# test.net
KiCad netlist of a schematic drawn in Altium Designer
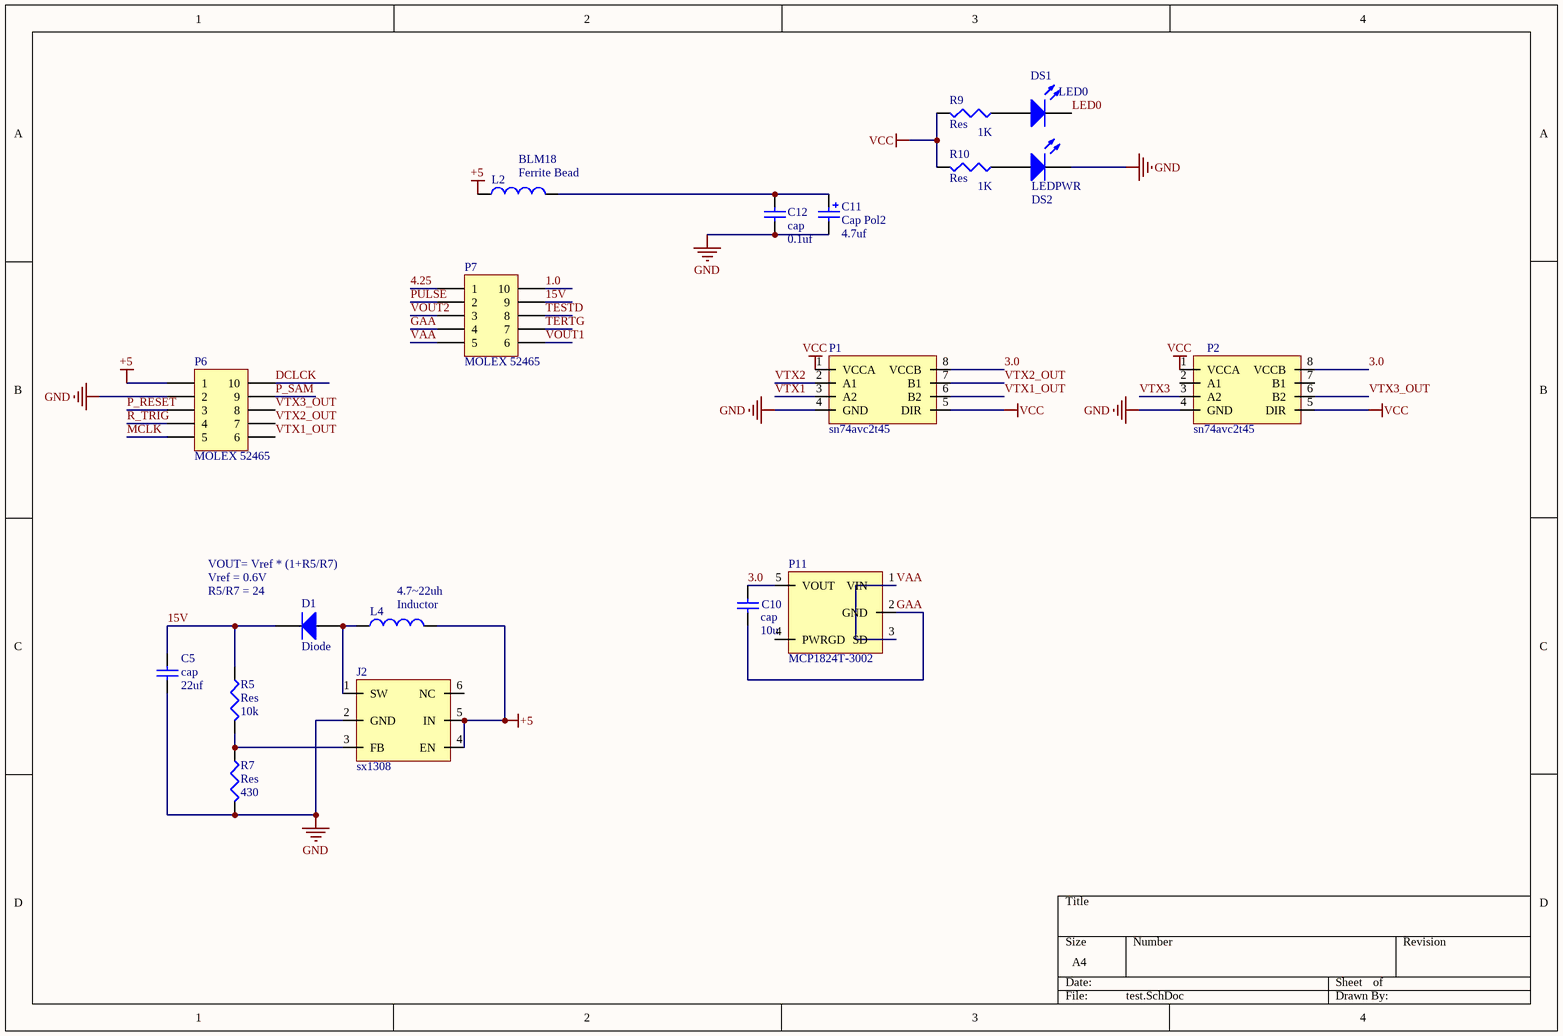
[diagram p0: test.SchDoc]

(export (version "E")
  (design (tool "Eeschema 10.0.6"))
  (components
    (comp (ref "C5")
      (value "cap")
      (footprint "J1-0603")
      (description "Capacitor (Semiconductor SIM Model)")
      (fields (field (name "ALTIUM_VALUE") "22uf") (field (name "PUBLISHER") "Altium Limited"))
      (libsource (lib "Miscellaneous Devices") (part "Cap Semi"))
    )
    (comp (ref "C10")
      (value "cap")
      (footprint "J1-0603")
      (description "Capacitor (Semiconductor SIM Model)")
      (fields (field (name "ALTIUM_VALUE") "10u") (field (name "PUBLISHER") "Altium Limited"))
      (libsource (lib "Miscellaneous Devices") (part "Cap Semi"))
    )
    (comp (ref "C11")
      (value "Cap Pol2")
      (footprint "C1206+")
      (description "Polarized Capacitor (Axial)")
      (fields (field (name "ALTIUM_VALUE") "4.7uf") (field (name "PUBLISHER") "Altium Limited"))
      (libsource (lib "Miscellaneous Devices") (part "Cap Pol2"))
    )
    (comp (ref "C12")
      (value "cap")
      (footprint "J1-0603")
      (description "Capacitor (Semiconductor SIM Model)")
      (fields (field (name "ALTIUM_VALUE") "0.1uf") (field (name "PUBLISHER") "Altium Limited"))
      (libsource (lib "Miscellaneous Devices") (part "Cap Semi"))
    )
    (comp (ref "D1")
      (value "Diode")
      (footprint "D1206")
      (description "Default Diode")
      (fields (field (name "PUBLISHER") "Altium Limited"))
      (libsource (lib "Miscellaneous Devices") (part "Diode"))
    )
    (comp (ref "DS1")
      (value "LED0")
      (footprint "SMDLED")
      (description "Typical RED, GREEN, YELLOW, AMBER GaAs LED")
      (fields (field (name "PUBLISHER") "Altium Limited"))
      (libsource (lib "2014ﾄ鷭STM32F4 Exploerｿｪｷ｢ｰ・V1.4_ｽﾌｳﾌﾂﾒｸﾄｰ觸EXPLORER") (part "LED2"))
    )
    (comp (ref "DS2")
      (value "LEDPWR")
      (footprint "SMDLED")
      (description "Typical RED, GREEN, YELLOW, AMBER GaAs LED")
      (fields (field (name "PUBLISHER") "Altium Limited"))
      (libsource (lib "2014ﾄ鷭STM32F4 Exploerｿｪｷ｢ｰ・V1.4_ｽﾌｳﾌﾂﾒｸﾄｰ觸EXPLORER") (part "LED2"))
    )
    (comp (ref "J2") (value "sx1308") (footprint "sot23-6") (libsource (lib "jskschemlib") (part "sx1308")))
    (comp (ref "L2")
      (value "Ferrite Bead")
      (footprint "J1-0603")
      (description "Inductor")
      (fields (field (name "ALTIUM_VALUE") "BLM18") (field (name "PUBLISHER") "Altium Limited"))
      (libsource (lib "Miscellaneous Devices") (part "Inductor"))
    )
    (comp (ref "L4")
      (value "Inductor")
      (footprint "induct4*4")
      (fields (field (name "ALTIUM_VALUE") "4.7~22uh") (field (name "PUBLISHER") "Altium Limited"))
      (libsource (lib "Miscellaneous Devices") (part "Inductor"))
    )
    (comp (ref "P1")
      (value "sn74avc2t45")
      (footprint "TSSOP8")
      (libsource (lib "jskschemlib") (part "sn74avc2t45"))
    )
    (comp (ref "P2")
      (value "sn74avc2t45")
      (footprint "TSSOP8")
      (libsource (lib "jskschemlib") (part "sn74avc2t45"))
    )
    (comp (ref "P6")
      (value "MOLEX 52465")
      (footprint "btb10p_m")
      (libsource (lib "jskschemlib") (part "header10"))
    )
    (comp (ref "P7")
      (value "MOLEX 52465")
      (footprint "btb10p_m")
      (libsource (lib "jskschemlib") (part "header10"))
    )
    (comp (ref "P11")
      (value "MCP1824T-3002")
      (footprint "SOT-23")
      (libsource (lib "jskschemlib") (part "VOLTREG"))
    )
    (comp (ref "R5")
      (value "Res")
      (footprint "J1-0603")
      (description "Resistor")
      (fields (field (name "ALTIUM_VALUE") "10k") (field (name "PUBLISHER") "Altium Limited"))
      (libsource (lib "Miscellaneous Devices") (part "Res3"))
    )
    (comp (ref "R7")
      (value "Res")
      (footprint "J1-0603")
      (description "Resistor")
      (fields (field (name "ALTIUM_VALUE") "430") (field (name "PUBLISHER") "Altium Limited"))
      (libsource (lib "Miscellaneous Devices") (part "Res3"))
    )
    (comp (ref "R9")
      (value "Res")
      (footprint "J1-0603")
      (description "Resistor")
      (fields (field (name "ALTIUM_VALUE") "1K") (field (name "PUBLISHER") "Altium Limited"))
      (libsource (lib "Miscellaneous Devices") (part "Res3"))
    )
    (comp (ref "R10")
      (value "Res")
      (footprint "J1-0603")
      (description "Resistor")
      (fields (field (name "ALTIUM_VALUE") "1K") (field (name "PUBLISHER") "Altium Limited"))
      (libsource (lib "Miscellaneous Devices") (part "Res3"))
    )
  )
  (nets
    (net (code "1") (name "+5") (class "Default")
      (node (ref "J2") (pin "4") (pinfunction "EN_4") (pintype "passive"))
      (node (ref "J2") (pin "5") (pinfunction "IN_5") (pintype "passive"))
      (node (ref "L2") (pin "1") (pinfunction "1_1") (pintype "passive"))
      (node (ref "L4") (pin "2") (pinfunction "2_2") (pintype "passive"))
      (node (ref "P6") (pin "1") (pinfunction "1_1") (pintype "passive"))
    )
    (net (code "2") (name "/1.0") (class "Default")
      (node (ref "P7") (pin "10") (pinfunction "10_10") (pintype "passive"))
    )
    (net (code "3") (name "/3.0") (class "Default")
      (node (ref "C10") (pin "2") (pinfunction "2_2") (pintype "passive"))
      (node (ref "P1") (pin "8") (pinfunction "VCCB_8") (pintype "passive"))
      (node (ref "P11") (pin "5") (pinfunction "VOUT_5") (pintype "passive"))
      (node (ref "P2") (pin "8") (pinfunction "VCCB_8") (pintype "passive"))
    )
    (net (code "4") (name "/4.25") (class "Default")
      (node (ref "P7") (pin "1") (pinfunction "1_1") (pintype "passive"))
    )
    (net (code "5") (name "/15V") (class "Default")
      (node (ref "C5") (pin "2") (pinfunction "2_2") (pintype "passive"))
      (node (ref "D1") (pin "2") (pinfunction "K_2") (pintype "passive"))
      (node (ref "P7") (pin "9") (pinfunction "9_9") (pintype "passive"))
      (node (ref "R5") (pin "1") (pinfunction "1_1") (pintype "passive"))
    )
    (net (code "6") (name "/DCLCK") (class "Default")
      (node (ref "P6") (pin "10") (pinfunction "10_10") (pintype "passive"))
    )
    (net (code "7") (name "/GAA") (class "Default")
      (node (ref "C10") (pin "1") (pinfunction "1_1") (pintype "passive"))
      (node (ref "P11") (pin "2") (pinfunction "GND_2") (pintype "passive"))
      (node (ref "P7") (pin "4") (pinfunction "4_4") (pintype "passive"))
    )
    (net (code "8") (name "/LED0") (class "Default")
      (node (ref "DS1") (pin "2") (pinfunction "K_2") (pintype "passive"))
    )
    (net (code "9") (name "/MCLK") (class "Default")
      (node (ref "P6") (pin "5") (pinfunction "5_5") (pintype "passive"))
    )
    (net (code "10") (name "/PULSE") (class "Default")
      (node (ref "P7") (pin "2") (pinfunction "2_2") (pintype "passive"))
    )
    (net (code "11") (name "/P_RESET") (class "Default")
      (node (ref "P6") (pin "3") (pinfunction "3_3") (pintype "passive"))
    )
    (net (code "12") (name "/P_SAM") (class "Default")
      (node (ref "P6") (pin "9") (pinfunction "9_9") (pintype "passive"))
    )
    (net (code "13") (name "/R_TRIG") (class "Default")
      (node (ref "P6") (pin "4") (pinfunction "4_4") (pintype "passive"))
    )
    (net (code "14") (name "/TERTG") (class "Default")
      (node (ref "P7") (pin "7") (pinfunction "7_7") (pintype "passive"))
    )
    (net (code "15") (name "/TESTD") (class "Default")
      (node (ref "P7") (pin "8") (pinfunction "8_8") (pintype "passive"))
    )
    (net (code "16") (name "/VAA") (class "Default")
      (node (ref "P11") (pin "1") (pinfunction "VIN_1") (pintype "passive"))
      (node (ref "P11") (pin "3") (pinfunction "SD_3") (pintype "passive"))
      (node (ref "P7") (pin "5") (pinfunction "5_5") (pintype "passive"))
    )
    (net (code "17") (name "/VOUT1") (class "Default")
      (node (ref "P7") (pin "6") (pinfunction "6_6") (pintype "passive"))
    )
    (net (code "18") (name "/VOUT2") (class "Default")
      (node (ref "P7") (pin "3") (pinfunction "3_3") (pintype "passive"))
    )
    (net (code "19") (name "/VTX1") (class "Default")
      (node (ref "P1") (pin "3") (pinfunction "A2_3") (pintype "passive"))
    )
    (net (code "20") (name "/VTX1_OUT") (class "Default")
      (node (ref "P1") (pin "6") (pinfunction "B2_6") (pintype "passive"))
      (node (ref "P6") (pin "6") (pinfunction "6_6") (pintype "passive"))
    )
    (net (code "21") (name "/VTX2") (class "Default")
      (node (ref "P1") (pin "2") (pinfunction "A1_2") (pintype "passive"))
    )
    (net (code "22") (name "/VTX2_OUT") (class "Default")
      (node (ref "P1") (pin "7") (pinfunction "B1_7") (pintype "passive"))
      (node (ref "P6") (pin "7") (pinfunction "7_7") (pintype "passive"))
    )
    (net (code "23") (name "/VTX3") (class "Default")
      (node (ref "P2") (pin "3") (pinfunction "A2_3") (pintype "passive"))
    )
    (net (code "24") (name "/VTX3_OUT") (class "Default")
      (node (ref "P2") (pin "6") (pinfunction "B2_6") (pintype "passive"))
      (node (ref "P6") (pin "8") (pinfunction "8_8") (pintype "passive"))
    )
    (net (code "25") (name "GND") (class "Default")
      (node (ref "C11") (pin "2") (pinfunction "2_2") (pintype "passive"))
      (node (ref "C12") (pin "1") (pinfunction "1_1") (pintype "passive"))
      (node (ref "C5") (pin "1") (pinfunction "1_1") (pintype "passive"))
      (node (ref "DS2") (pin "2") (pinfunction "K_2") (pintype "passive"))
      (node (ref "J2") (pin "2") (pinfunction "GND_2") (pintype "passive"))
      (node (ref "P1") (pin "4") (pinfunction "GND_4") (pintype "passive"))
      (node (ref "P2") (pin "4") (pinfunction "GND_4") (pintype "passive"))
      (node (ref "P6") (pin "2") (pinfunction "2_2") (pintype "passive"))
      (node (ref "R7") (pin "2") (pinfunction "2_2") (pintype "passive"))
    )
    (net (code "26") (name "Net-(C11-Pad1)") (class "Default")
      (node (ref "C11") (pin "1") (pinfunction "1_1") (pintype "passive"))
      (node (ref "C12") (pin "2") (pinfunction "2_2") (pintype "passive"))
      (node (ref "L2") (pin "2") (pinfunction "2_2") (pintype "passive"))
    )
    (net (code "27") (name "Net-(D1-A)") (class "Default")
      (node (ref "D1") (pin "1") (pinfunction "A_1") (pintype "passive"))
      (node (ref "J2") (pin "1") (pinfunction "SW_1") (pintype "passive"))
      (node (ref "L4") (pin "1") (pinfunction "1_1") (pintype "passive"))
    )
    (net (code "28") (name "Net-(DS1-A)") (class "Default")
      (node (ref "DS1") (pin "1") (pinfunction "A_1") (pintype "passive"))
      (node (ref "R9") (pin "1") (pinfunction "1_1") (pintype "passive"))
    )
    (net (code "29") (name "Net-(DS2-A)") (class "Default")
      (node (ref "DS2") (pin "1") (pinfunction "A_1") (pintype "passive"))
      (node (ref "R10") (pin "1") (pinfunction "1_1") (pintype "passive"))
    )
    (net (code "30") (name "Net-(J2-FB)") (class "Default")
      (node (ref "J2") (pin "3") (pinfunction "FB_3") (pintype "passive"))
      (node (ref "R5") (pin "2") (pinfunction "2_2") (pintype "passive"))
      (node (ref "R7") (pin "1") (pinfunction "1_1") (pintype "passive"))
    )
    (net (code "31") (name "VCC") (class "Default")
      (node (ref "P1") (pin "1") (pinfunction "VCCA_1") (pintype "passive"))
      (node (ref "P1") (pin "5") (pinfunction "DIR_5") (pintype "passive"))
      (node (ref "P2") (pin "1") (pinfunction "VCCA_1") (pintype "passive"))
      (node (ref "P2") (pin "5") (pinfunction "DIR_5") (pintype "passive"))
      (node (ref "R10") (pin "2") (pinfunction "2_2") (pintype "passive"))
      (node (ref "R9") (pin "2") (pinfunction "2_2") (pintype "passive"))
    )
    (net (code "32") (name "unconnected-(J2-NC-Pad6)") (class "Default")
      (node (ref "J2") (pin "6") (pinfunction "NC_6") (pintype "passive"))
    )
    (net (code "33") (name "unconnected-(P2-A1-Pad2)") (class "Default")
      (node (ref "P2") (pin "2") (pinfunction "A1_2") (pintype "passive"))
    )
    (net (code "34") (name "unconnected-(P2-B1-Pad7)") (class "Default")
      (node (ref "P2") (pin "7") (pinfunction "B1_7") (pintype "passive"))
    )
    (net (code "35") (name "unconnected-(P11-PWRGD-Pad4)") (class "Default")
      (node (ref "P11") (pin "4") (pinfunction "PWRGD_4") (pintype "passive"))
    )
  )
)
